# gabemon.net
KiCad netlist of a schematic drawn in EAGLE
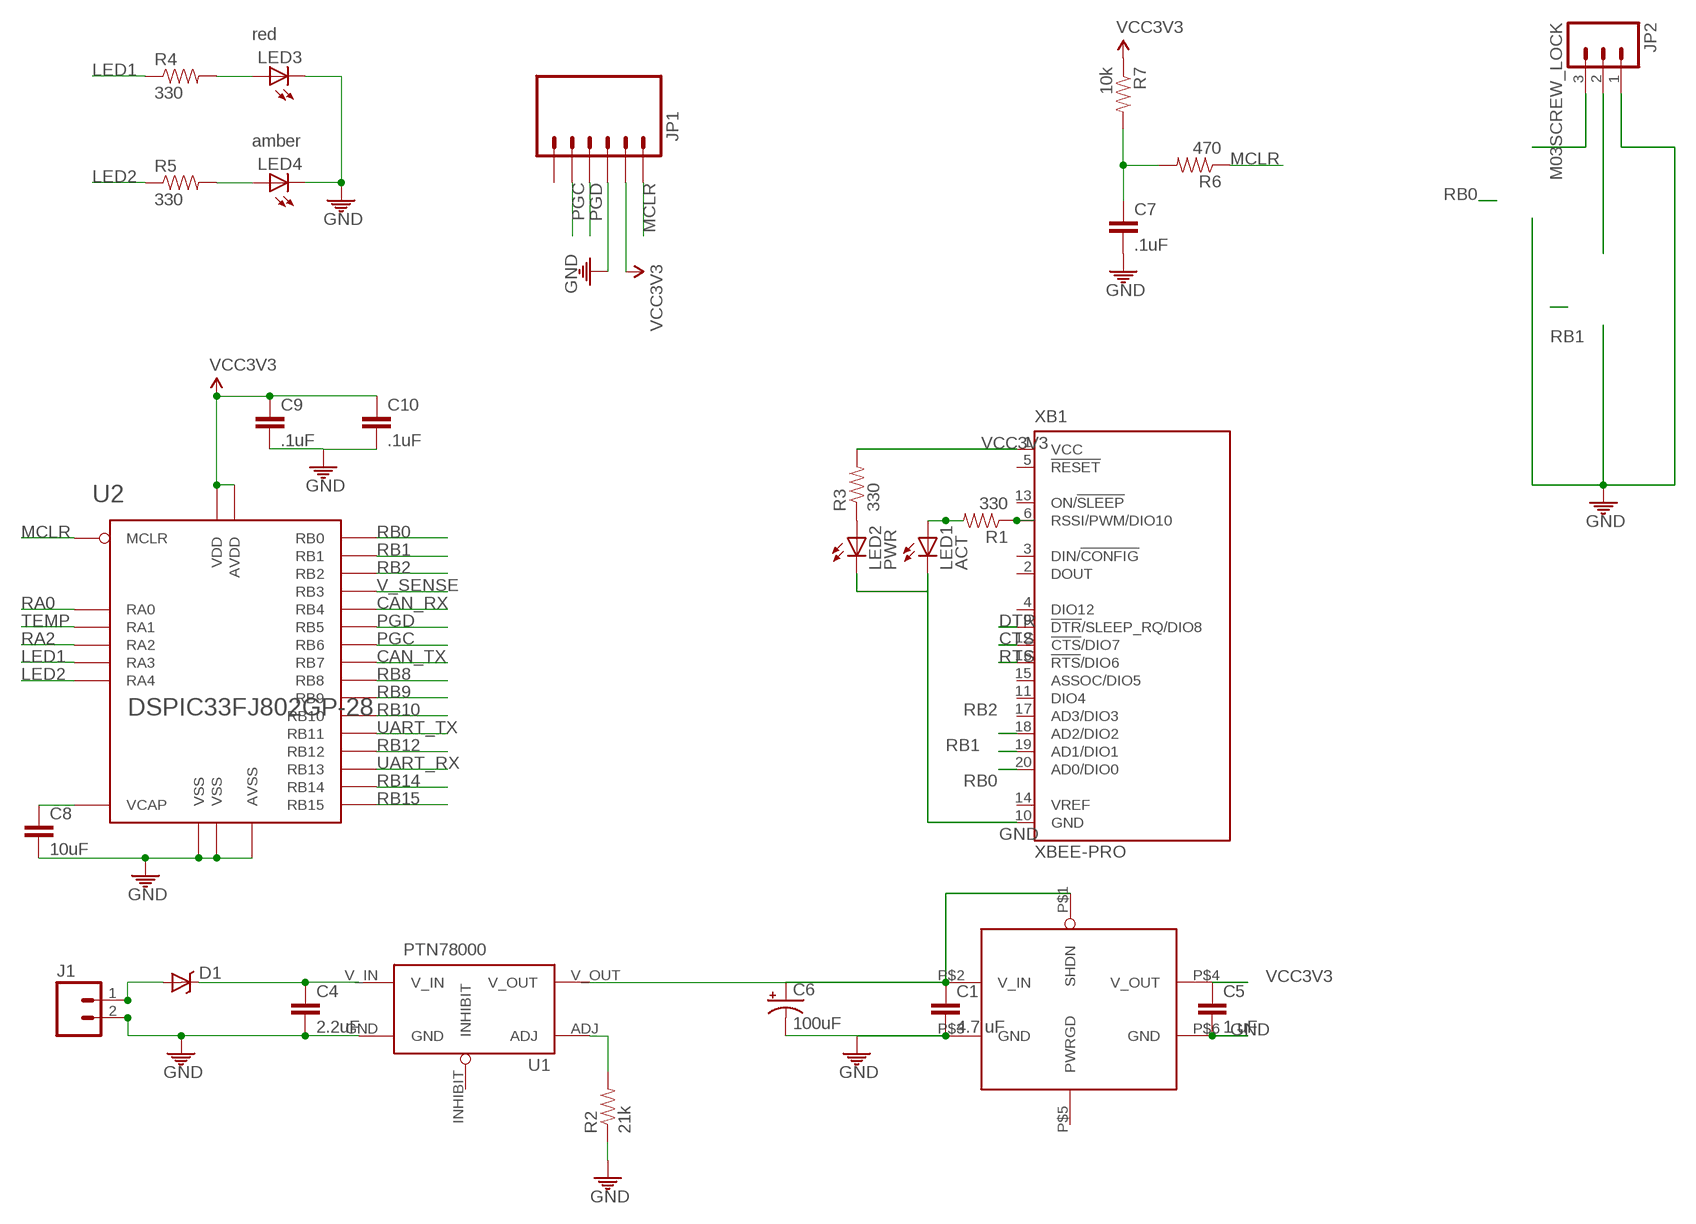
[diagram p0: schematic, sheet 1]

(export (version "E")
  (design (tool "Eeschema 10.0.6"))
  (components
    (comp (ref "C1")
      (value "4.7 uF")
      (footprint "eagle-import:1206")
      (libsource (lib "eagle-import") (part "CAP1206"))
    )
    (comp (ref "C4")
      (value "2.2uF")
      (footprint "eagle-import:1206")
      (libsource (lib "eagle-import") (part "CMPE118lib_CAP1206"))
    )
    (comp (ref "C5")
      (value "1 uF")
      (footprint "eagle-import:1206")
      (libsource (lib "eagle-import") (part "CAP1206"))
    )
    (comp (ref "C6")
      (value "100uF")
      (footprint "eagle-import:CPOL_6.6")
      (libsource (lib "eagle-import") (part "CAP_POL"))
    )
    (comp (ref "C7")
      (value ".1uF")
      (footprint "eagle-import:1206")
      (libsource (lib "eagle-import") (part "CMPE118lib_CAP1206"))
    )
    (comp (ref "C8")
      (value "10uF")
      (footprint "eagle-import:1206")
      (libsource (lib "eagle-import") (part "CMPE118lib_CAP1206"))
    )
    (comp (ref "C9")
      (value ".1uF")
      (footprint "eagle-import:1206")
      (libsource (lib "eagle-import") (part "CMPE118lib_CAP1206"))
    )
    (comp (ref "C10")
      (value ".1uF")
      (footprint "eagle-import:1206")
      (libsource (lib "eagle-import") (part "CMPE118lib_CAP1206"))
    )
    (comp (ref "D1")
      (value "DIODE-SCHOTTKY240A")
      (footprint "eagle-import:SMA-DIODE-B240A")
      (libsource (lib "eagle-import") (part "DIODE-SCHOTTKY240A"))
    )
    (comp (ref "J1")
      (value "M023.5MM-NO_SILK")
      (footprint "eagle-import:SCREWTERMINAL-3.5MM-2-NS")
      (libsource (lib "eagle-import") (part "M023.5MM-NO_SILK"))
    )
    (comp (ref "JP1")
      (value "M06LOCK")
      (footprint "eagle-import:1X06_LOCK")
      (libsource (lib "eagle-import") (part "M06LOCK"))
    )
    (comp (ref "JP2")
      (value "M03SCREW_LOCK")
      (footprint "eagle-import:SCREWTERMINAL-3.5MM-3_LOCK.007S")
      (libsource (lib "eagle-import") (part "M03SCREW_LOCK"))
    )
    (comp (ref "LED1")
      (value "ACT")
      (footprint "eagle-import:LED-1206")
      (libsource (lib "eagle-import") (part "LED1206"))
    )
    (comp (ref "LED2")
      (value "PWR")
      (footprint "eagle-import:LED-1206")
      (libsource (lib "eagle-import") (part "LED1206"))
    )
    (comp (ref "LED3")
      (value "LED1206")
      (footprint "eagle-import:LED-1206")
      (fields (field (name "COLOR") "red"))
      (libsource (lib "eagle-import") (part "CMPE118lib_LED1206"))
    )
    (comp (ref "LED4")
      (value "LED1206")
      (footprint "eagle-import:LED-1206")
      (fields (field (name "COLOR") "amber"))
      (libsource (lib "eagle-import") (part "CMPE118lib_LED1206"))
    )
    (comp (ref "R1")
      (value "330")
      (footprint "eagle-import:0805")
      (libsource (lib "eagle-import") (part "RESISTOR0805-RES"))
    )
    (comp (ref "R2")
      (value "21k")
      (footprint "eagle-import:0805")
      (libsource (lib "eagle-import") (part "CMPE118lib_RESISTOR0805-RES"))
    )
    (comp (ref "R3")
      (value "330")
      (footprint "eagle-import:0805")
      (libsource (lib "eagle-import") (part "RESISTOR0805-RES"))
    )
    (comp (ref "R4")
      (value "330")
      (footprint "eagle-import:0805")
      (libsource (lib "eagle-import") (part "CMPE118lib_RESISTOR0805-RES"))
    )
    (comp (ref "R5")
      (value "330")
      (footprint "eagle-import:0805")
      (libsource (lib "eagle-import") (part "CMPE118lib_RESISTOR0805-RES"))
    )
    (comp (ref "R6")
      (value "470")
      (footprint "eagle-import:0805")
      (libsource (lib "eagle-import") (part "CMPE118lib_RESISTOR0805-RES"))
    )
    (comp (ref "R7")
      (value "10k")
      (footprint "eagle-import:0805")
      (libsource (lib "eagle-import") (part "CMPE118lib_RESISTOR0805-RES"))
    )
    (comp (ref "U$2")
      (value "MCP1826")
      (footprint "eagle-import:SOT223-5")
      (libsource (lib "eagle-import") (part "MCP1826"))
    )
    (comp (ref "U1")
      (value "PTN78000")
      (footprint "eagle-import:PTN78000")
      (libsource (lib "eagle-import") (part "PTN78000THROUGH-HOLE"))
    )
    (comp (ref "U2")
      (value "DSPIC33FJ802GP-28")
      (footprint "eagle-import:SOIC28-W")
      (libsource (lib "eagle-import") (part "DSPIC33FJ802GP-28"))
    )
    (comp (ref "XB1")
      (value "XBEE-PRO")
      (footprint "eagle-import:XBEE-PRO")
      (fields (field (name "MPN") "XBP24-AWI-001"))
      (libsource (lib "eagle-import") (part "XBEE-PRO"))
    )
  )
  (nets
    (net (code "1") (name "/CAN_RX") (class "Default")
      (node (ref "U2") (pin "P$11") (pinfunction "RB4_P$11") (pintype "bidirectional"))
    )
    (net (code "2") (name "/CAN_TX") (class "Default")
      (node (ref "U2") (pin "P$16") (pinfunction "RB7_P$16") (pintype "bidirectional"))
    )
    (net (code "3") (name "/CTS") (class "Default")
      (node (ref "XB1") (pin "12") (pinfunction "~{CTS}/DIO7_12") (pintype "bidirectional"))
    )
    (net (code "4") (name "/DTR") (class "Default")
      (node (ref "XB1") (pin "9") (pinfunction "~{DTR}/SLEEP_RQ/DIO8_9") (pintype "bidirectional"))
    )
    (net (code "5") (name "/LED1") (class "Default")
      (node (ref "R4") (pin "1") (pinfunction "1_1") (pintype "passive"))
      (node (ref "U2") (pin "P$10") (pinfunction "RA3_P$10") (pintype "bidirectional"))
    )
    (net (code "6") (name "/LED2") (class "Default")
      (node (ref "R5") (pin "1") (pinfunction "1_1") (pintype "passive"))
      (node (ref "U2") (pin "P$12") (pinfunction "RA4_P$12") (pintype "bidirectional"))
    )
    (net (code "7") (name "/MCLR") (class "Default")
      (node (ref "JP1") (pin "1") (pinfunction "1_1") (pintype "passive"))
      (node (ref "R6") (pin "1") (pinfunction "1_1") (pintype "passive"))
      (node (ref "U2") (pin "P$1") (pinfunction "MCLR_P$1") (pintype "bidirectional"))
    )
    (net (code "8") (name "/PGC") (class "Default")
      (node (ref "JP1") (pin "5") (pinfunction "5_5") (pintype "passive"))
      (node (ref "U2") (pin "P$15") (pinfunction "RB6_P$15") (pintype "bidirectional"))
    )
    (net (code "9") (name "/PGD") (class "Default")
      (node (ref "JP1") (pin "4") (pinfunction "4_4") (pintype "passive"))
      (node (ref "U2") (pin "P$14") (pinfunction "RB5_P$14") (pintype "bidirectional"))
    )
    (net (code "10") (name "/RA0") (class "Default")
      (node (ref "U2") (pin "P$2") (pinfunction "RA0_P$2") (pintype "bidirectional"))
    )
    (net (code "11") (name "/RA2") (class "Default")
      (node (ref "U2") (pin "P$9") (pinfunction "RA2_P$9") (pintype "bidirectional"))
    )
    (net (code "12") (name "/RB0") (class "Default")
      (node (ref "U2") (pin "P$4") (pinfunction "RB0_P$4") (pintype "bidirectional"))
      (node (ref "XB1") (pin "20") (pinfunction "AD0/DIO0_20") (pintype "bidirectional"))
    )
    (net (code "13") (name "/RB1") (class "Default")
      (node (ref "U2") (pin "P$5") (pinfunction "RB1_P$5") (pintype "bidirectional"))
      (node (ref "XB1") (pin "19") (pinfunction "AD1/DIO1_19") (pintype "bidirectional"))
    )
    (net (code "14") (name "/RB2") (class "Default")
      (node (ref "U2") (pin "P$6") (pinfunction "RB2_P$6") (pintype "bidirectional"))
      (node (ref "XB1") (pin "18") (pinfunction "AD2/DIO2_18") (pintype "bidirectional"))
    )
    (net (code "15") (name "/RB8") (class "Default")
      (node (ref "U2") (pin "P$17") (pinfunction "RB8_P$17") (pintype "bidirectional"))
    )
    (net (code "16") (name "/RB9") (class "Default")
      (node (ref "U2") (pin "P$18") (pinfunction "RB9_P$18") (pintype "bidirectional"))
    )
    (net (code "17") (name "/RB10") (class "Default")
      (node (ref "U2") (pin "P$22") (pinfunction "RB10_P$22") (pintype "bidirectional"))
    )
    (net (code "18") (name "/RB12") (class "Default")
      (node (ref "U2") (pin "P$23") (pinfunction "RB12_P$23") (pintype "bidirectional"))
    )
    (net (code "19") (name "/RB14") (class "Default")
      (node (ref "U2") (pin "P$25") (pinfunction "RB14_P$25") (pintype "bidirectional"))
    )
    (net (code "20") (name "/RB15") (class "Default")
      (node (ref "U2") (pin "P$26") (pinfunction "RB15_P$26") (pintype "bidirectional"))
    )
    (net (code "21") (name "/RTS") (class "Default")
      (node (ref "XB1") (pin "16") (pinfunction "~{RTS}/DIO6_16") (pintype "bidirectional"))
    )
    (net (code "22") (name "/TEMP") (class "Default")
      (node (ref "U2") (pin "P$3") (pinfunction "RA1_P$3") (pintype "bidirectional"))
    )
    (net (code "23") (name "/UART_RX") (class "Default")
      (node (ref "U2") (pin "P$24") (pinfunction "RB13_P$24") (pintype "bidirectional"))
    )
    (net (code "24") (name "/UART_TX") (class "Default")
      (node (ref "U2") (pin "P$21") (pinfunction "RB11_P$21") (pintype "bidirectional"))
    )
    (net (code "25") (name "/V_SENSE") (class "Default")
      (node (ref "U2") (pin "P$7") (pinfunction "RB3_P$7") (pintype "bidirectional"))
    )
    (net (code "26") (name "GND") (class "Default")
      (node (ref "C1") (pin "2") (pinfunction "2_2") (pintype "passive"))
      (node (ref "C10") (pin "2") (pinfunction "2_2") (pintype "passive"))
      (node (ref "C4") (pin "2") (pinfunction "2_2") (pintype "passive"))
      (node (ref "C5") (pin "2") (pinfunction "2_2") (pintype "passive"))
      (node (ref "C6") (pin "-") (pinfunction "-_-") (pintype "passive"))
      (node (ref "C7") (pin "2") (pinfunction "2_2") (pintype "passive"))
      (node (ref "C8") (pin "2") (pinfunction "2_2") (pintype "passive"))
      (node (ref "C9") (pin "2") (pinfunction "2_2") (pintype "passive"))
      (node (ref "J1") (pin "2") (pinfunction "1_2") (pintype "passive"))
      (node (ref "JP1") (pin "3") (pinfunction "3_3") (pintype "passive"))
      (node (ref "JP2") (pin "1") (pinfunction "1_1") (pintype "passive"))
      (node (ref "LED1") (pin "C") (pinfunction "C_C") (pintype "passive"))
      (node (ref "LED2") (pin "C") (pinfunction "C_C") (pintype "passive"))
      (node (ref "LED3") (pin "C") (pinfunction "C_C") (pintype "passive"))
      (node (ref "LED4") (pin "C") (pinfunction "C_C") (pintype "passive"))
      (node (ref "R2") (pin "1") (pinfunction "1_1") (pintype "passive"))
      (node (ref "U$2") (pin "P$3") (pinfunction "GND_P$3") (pintype "power_in"))
      (node (ref "U$2") (pin "P$6") (pinfunction "GND_P$6") (pintype "power_in"))
      (node (ref "U1") (pin "GND") (pinfunction "GND_GND") (pintype "power_in"))
      (node (ref "U2") (pin "P$19") (pinfunction "VSS_P$19") (pintype "power_in"))
      (node (ref "U2") (pin "P$27") (pinfunction "AVSS_P$27") (pintype "input"))
      (node (ref "U2") (pin "P$8") (pinfunction "VSS_P$8") (pintype "power_in"))
      (node (ref "XB1") (pin "10") (pinfunction "GND_10") (pintype "power_in"))
    )
    (net (code "27") (name "Net-(C4-Pad1)") (class "Default")
      (node (ref "C4") (pin "1") (pinfunction "1_1") (pintype "passive"))
      (node (ref "D1") (pin "C") (pinfunction "C_C") (pintype "passive"))
      (node (ref "U1") (pin "V_IN") (pinfunction "V_IN_V_IN") (pintype "power_in"))
    )
    (net (code "28") (name "Net-(C7-Pad1)") (class "Default")
      (node (ref "C7") (pin "1") (pinfunction "1_1") (pintype "passive"))
      (node (ref "R6") (pin "2") (pinfunction "2_2") (pintype "passive"))
      (node (ref "R7") (pin "2") (pinfunction "2_2") (pintype "passive"))
    )
    (net (code "29") (name "Net-(J1-2)") (class "Default")
      (node (ref "D1") (pin "A") (pinfunction "A_A") (pintype "passive"))
      (node (ref "J1") (pin "1") (pinfunction "2_1") (pintype "passive"))
    )
    (net (code "30") (name "Net-(LED1-PadA)") (class "Default")
      (node (ref "LED1") (pin "A") (pinfunction "A_A") (pintype "passive"))
      (node (ref "R1") (pin "2") (pinfunction "2_2") (pintype "passive"))
    )
    (net (code "31") (name "Net-(LED2-PadA)") (class "Default")
      (node (ref "LED2") (pin "A") (pinfunction "A_A") (pintype "passive"))
      (node (ref "R3") (pin "1") (pinfunction "1_1") (pintype "passive"))
    )
    (net (code "32") (name "Net-(LED3-PadA)") (class "Default")
      (node (ref "LED3") (pin "A") (pinfunction "A_A") (pintype "passive"))
      (node (ref "R4") (pin "2") (pinfunction "2_2") (pintype "passive"))
    )
    (net (code "33") (name "Net-(LED4-PadA)") (class "Default")
      (node (ref "LED4") (pin "A") (pinfunction "A_A") (pintype "passive"))
      (node (ref "R5") (pin "2") (pinfunction "2_2") (pintype "passive"))
    )
    (net (code "34") (name "Net-(R2-Pad2)") (class "Default")
      (node (ref "R2") (pin "2") (pinfunction "2_2") (pintype "passive"))
      (node (ref "U1") (pin "ADJ") (pinfunction "ADJ_ADJ") (pintype "input"))
    )
    (net (code "35") (name "Net-(U$2-SHDN)") (class "Default")
      (node (ref "C1") (pin "1") (pinfunction "1_1") (pintype "passive"))
      (node (ref "C6") (pin "+") (pinfunction "+_+") (pintype "passive"))
      (node (ref "U$2") (pin "P$1") (pinfunction "SHDN_P$1") (pintype "input"))
      (node (ref "U$2") (pin "P$2") (pinfunction "V_IN_P$2") (pintype "power_in"))
      (node (ref "U1") (pin "V_OUT") (pinfunction "V_OUT_V_OUT") (pintype "output"))
    )
    (net (code "36") (name "Net-(U2-VCAP)") (class "Default")
      (node (ref "C8") (pin "1") (pinfunction "1_1") (pintype "passive"))
      (node (ref "U2") (pin "P$20") (pinfunction "VCAP_P$20") (pintype "input"))
    )
    (net (code "37") (name "Net-(XB1-RSSI{slash}PWM{slash}DIO10)") (class "Default")
      (node (ref "R1") (pin "1") (pinfunction "1_1") (pintype "passive"))
      (node (ref "XB1") (pin "6") (pinfunction "RSSI/PWM/DIO10_6") (pintype "output"))
    )
    (net (code "38") (name "VCC3V3") (class "Default")
      (node (ref "C10") (pin "1") (pinfunction "1_1") (pintype "passive"))
      (node (ref "C5") (pin "1") (pinfunction "1_1") (pintype "passive"))
      (node (ref "C9") (pin "1") (pinfunction "1_1") (pintype "passive"))
      (node (ref "JP1") (pin "2") (pinfunction "2_2") (pintype "passive"))
      (node (ref "R3") (pin "2") (pinfunction "2_2") (pintype "passive"))
      (node (ref "R7") (pin "1") (pinfunction "1_1") (pintype "passive"))
      (node (ref "U$2") (pin "P$4") (pinfunction "V_OUT_P$4") (pintype "output"))
      (node (ref "U2") (pin "P$13") (pinfunction "VDD_P$13") (pintype "power_in"))
      (node (ref "U2") (pin "P$28") (pinfunction "AVDD_P$28") (pintype "input"))
      (node (ref "XB1") (pin "1") (pinfunction "VCC_1") (pintype "power_in"))
    )
    (net (code "39") (name "unconnected-(JP1-Pad6)") (class "Default")
      (node (ref "JP1") (pin "6") (pinfunction "6_6") (pintype "passive"))
    )
    (net (code "40") (name "unconnected-(JP2-Pad2)") (class "Default")
      (node (ref "JP2") (pin "2") (pinfunction "2_2") (pintype "passive"))
    )
    (net (code "41") (name "unconnected-(JP2-Pad3)") (class "Default")
      (node (ref "JP2") (pin "3") (pinfunction "3_3") (pintype "passive"))
    )
    (net (code "42") (name "unconnected-(U$2-PWRGD-PadP$5)") (class "Default")
      (node (ref "U$2") (pin "P$5") (pinfunction "PWRGD_P$5") (pintype "open_collector"))
    )
    (net (code "43") (name "unconnected-(U1-PadINHIBIT)") (class "Default")
      (node (ref "U1") (pin "INHIBIT") (pinfunction "INHIBIT_INHIBIT") (pintype "input"))
    )
    (net (code "44") (name "unconnected-(XB1-AD3{slash}DIO3-Pad17)") (class "Default")
      (node (ref "XB1") (pin "17") (pinfunction "AD3/DIO3_17") (pintype "bidirectional"))
    )
    (net (code "45") (name "unconnected-(XB1-ASSOC{slash}DIO5-Pad15)") (class "Default")
      (node (ref "XB1") (pin "15") (pinfunction "ASSOC/DIO5_15") (pintype "bidirectional"))
    )
    (net (code "46") (name "unconnected-(XB1-DIN{slash}~{CONFIG}-Pad3)") (class "Default")
      (node (ref "XB1") (pin "3") (pinfunction "DIN/~{CONFIG}_3") (pintype "input"))
    )
    (net (code "47") (name "unconnected-(XB1-DIO4-Pad11)") (class "Default")
      (node (ref "XB1") (pin "11") (pinfunction "DIO4_11") (pintype "bidirectional"))
    )
    (net (code "48") (name "unconnected-(XB1-DIO12-Pad4)") (class "Default")
      (node (ref "XB1") (pin "4") (pinfunction "DIO12_4") (pintype "bidirectional"))
    )
    (net (code "49") (name "unconnected-(XB1-DOUT-Pad2)") (class "Default")
      (node (ref "XB1") (pin "2") (pinfunction "DOUT_2") (pintype "output"))
    )
    (net (code "50") (name "unconnected-(XB1-ON{slash}~{SLEEP}-Pad13)") (class "Default")
      (node (ref "XB1") (pin "13") (pinfunction "ON/~{SLEEP}_13") (pintype "output"))
    )
    (net (code "51") (name "unconnected-(XB1-VREF-Pad14)") (class "Default")
      (node (ref "XB1") (pin "14") (pinfunction "VREF_14") (pintype "input"))
    )
    (net (code "52") (name "unconnected-(XB1-~{RESET}-Pad5)") (class "Default")
      (node (ref "XB1") (pin "5") (pinfunction "~{RESET}_5") (pintype "input"))
    )
  )
)
